# Sche_MCU_IO.net
KiCad netlist of a schematic drawn in Altium Designer
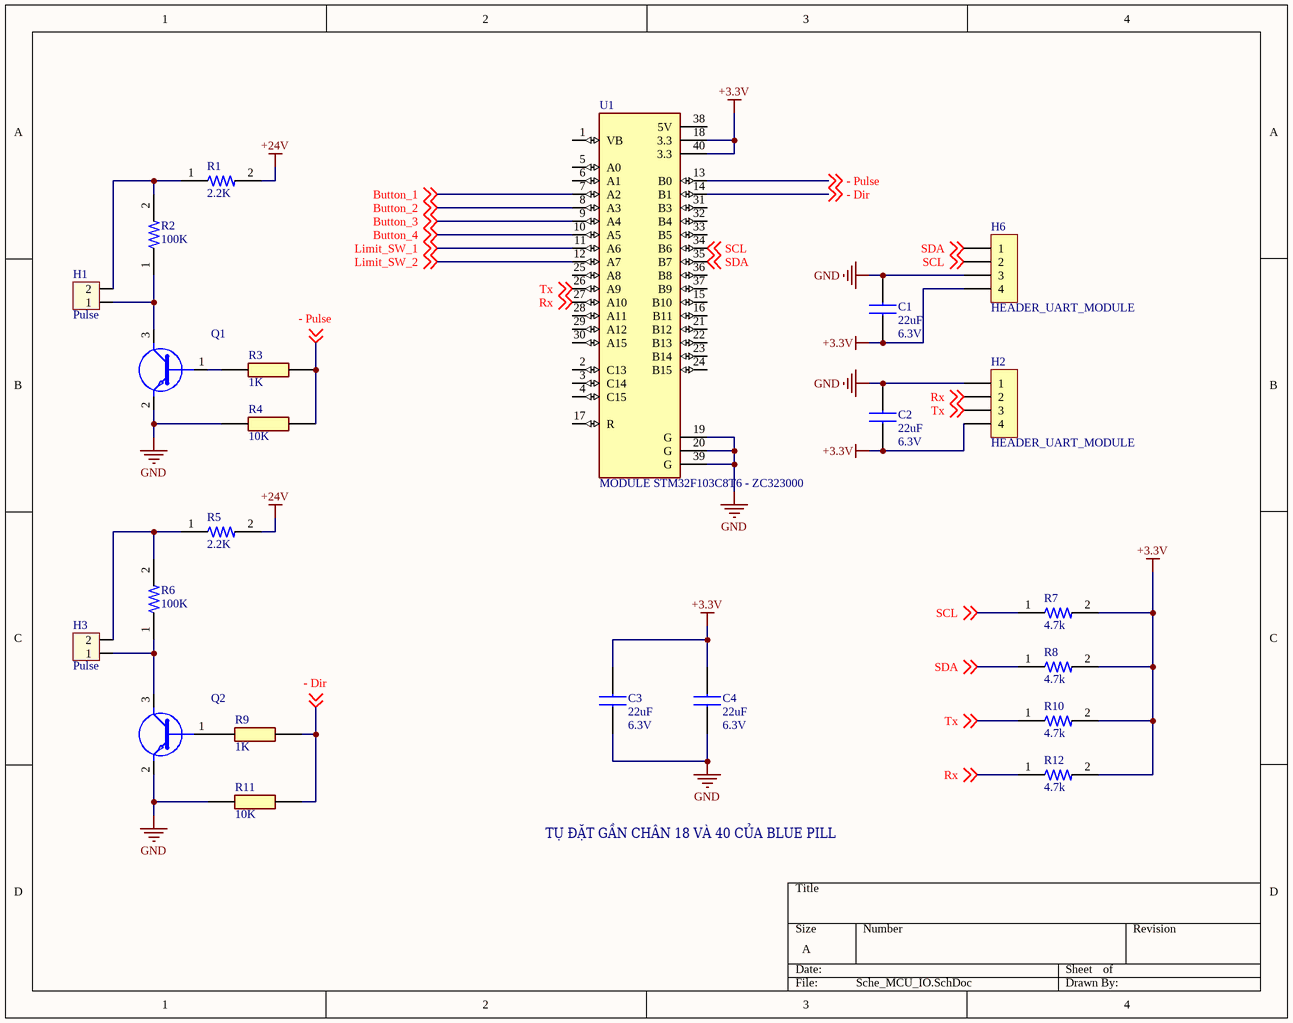
[diagram p0: Sche_MCU_IO.SchDoc]

(export (version "E")
  (design (tool "Eeschema 10.0.6"))
  (components
    (comp (ref "C1")
      (value "22uF")
      (footprint "PCB_COF_1.2:C 0603")
      (description "CAP CER 22UF 6.3V X5R 0603")
      (fields (field (name "ALTIUM_UNNAMED_1") "6.3V"))
      (libsource (lib "LAB_COATING COF_MACHINE") (part "CAP CER 22UF 6.3V X5R 0603 - GRM188R60J226MEA0D"))
    )
    (comp (ref "C2")
      (value "22uF")
      (footprint "PCB_COF_1.2:C 0603")
      (description "CAP CER 22UF 6.3V X5R 0603")
      (fields (field (name "ALTIUM_UNNAMED_1") "6.3V"))
      (libsource (lib "LAB_COATING COF_MACHINE") (part "CAP CER 22UF 6.3V X5R 0603 - GRM188R60J226MEA0D"))
    )
    (comp (ref "C3")
      (value "22uF")
      (footprint "PCB_COF_1.2:C 0603")
      (description "CAP CER 22UF 6.3V X5R 0603")
      (fields (field (name "ALTIUM_UNNAMED_1") "6.3V"))
      (libsource (lib "LAB_COATING COF_MACHINE") (part "CAP CER 22UF 6.3V X5R 0603 - GRM188R60J226MEA0D"))
    )
    (comp (ref "C4")
      (value "22uF")
      (footprint "PCB_COF_1.2:C 0603")
      (description "CAP CER 22UF 6.3V X5R 0603")
      (fields (field (name "ALTIUM_UNNAMED_1") "6.3V"))
      (libsource (lib "LAB_COATING COF_MACHINE") (part "CAP CER 22UF 6.3V X5R 0603 - GRM188R60J226MEA0D"))
    )
    (comp (ref "H1")
      (value "Pulse")
      (footprint "Header 2P DC 2.54")
      (description "Cắm")
      (libsource (lib "LAB_COATING COF_MACHINE") (part "Header 2P 2.54 Duc Cong"))
    )
    (comp (ref "H2")
      (value "HEADER_UART_MODULE")
      (footprint "XH2.54M-4")
      (description "Cắm")
      (libsource (lib "LAB_COATING COF_MACHINE") (part "Header 4P 2.54 Duc Thang"))
    )
    (comp (ref "H3")
      (value "Pulse")
      (footprint "Header 2P DC 2.54")
      (description "Cắm")
      (libsource (lib "LAB_COATING COF_MACHINE") (part "Header 2P 2.54 Duc Cong"))
    )
    (comp (ref "H6")
      (value "HEADER_UART_MODULE")
      (footprint "XH2.54M-4")
      (description "Cắm")
      (libsource (lib "LAB_COATING COF_MACHINE") (part "Header 4P 2.54 Duc Thang"))
    )
    (comp (ref "Q1")
      (value "TRANS NPN 45V 0.8A SOT23-3 - BCW66GLT1G")
      (footprint "SOT95P237X111-3N")
      (description "TRANS NPN 45V 0.8A SOT23-3")
      (fields
        (field (name "MANUFACTURER_PART_NUMBER") "BCW66GLT1G")
        (field (name "MOUSER PART NUMBER") "863-BCW66GLT1G")
      )
      (libsource (lib "LAB_COATING COF_MACHINE") (part "TRANS NPN 45V 0.8A SOT23-3 - BCW66GLT1G"))
    )
    (comp (ref "Q2")
      (value "TRANS NPN 45V 0.8A SOT23-3 - BCW66GLT1G")
      (footprint "SOT95P237X111-3N")
      (description "TRANS NPN 45V 0.8A SOT23-3")
      (fields
        (field (name "MANUFACTURER_PART_NUMBER") "BCW66GLT1G")
        (field (name "MOUSER PART NUMBER") "863-BCW66GLT1G")
      )
      (libsource (lib "LAB_COATING COF_MACHINE") (part "TRANS NPN 45V 0.8A SOT23-3 - BCW66GLT1G"))
    )
    (comp (ref "R1")
      (value "2.2K")
      (footprint "RES 0805")
      (description "RES SMD 2.2K OHM 5% 1/2W 0805")
      (fields (field (name "MP") "ERJ-P06J222V") (field (name "MF") "PANASONIC"))
      (libsource (lib "LAB_COATING COF_MACHINE") (part "RES SMD 2.2K OHM 5% 1/2W 0805 - ERJ-P06J222V"))
    )
    (comp (ref "R2")
      (value "100K")
      (footprint "Res 0603")
      (description "RES SMD 100K OHM 1% 1/10W 0603")
      (fields (field (name "MP") "CRCW0603100KFKEA") (field (name "MF") "Yageo"))
      (libsource (lib "LAB_COATING COF_MACHINE") (part "RES SMD 100K OHM 1% 1/10W 0603 - CRCW0603100KFKEA"))
    )
    (comp (ref "R3")
      (value "1K")
      (footprint "ERJ3EKF1000V")
      (description "RES SMD 1K OHM 5% 1/10W 0603")
      (fields
        (field (name "MANUFACTURER_PART_NUMBER") "ERJ-3GEYJ102V")
        (field (name "MOUSER PART NUMBER") "667-ERJ-3GEYJ102V")
      )
      (libsource (lib "LAB_COATING COF_MACHINE") (part "RES SMD 1K OHM 5% 1/10W 0603 - ERJ-3GEYJ102V"))
    )
    (comp (ref "R4")
      (value "10K")
      (footprint "ERJ3EKF1000V")
      (description "RES SMD 10K OHM 5% 1/10W 0603")
      (fields
        (field (name "MANUFACTURER_PART_NUMBER") "ERJ3GEYJ103V")
        (field (name "MOUSER PART NUMBER") "667-ERJ-3GEYJ103V")
      )
      (libsource (lib "LAB_COATING COF_MACHINE") (part "RES SMD 10K OHM 5% 1/10W 0603 - ERJ3GEYJ103V"))
    )
    (comp (ref "R5")
      (value "2.2K")
      (footprint "RES 0805")
      (description "RES SMD 2.2K OHM 5% 1/2W 0805")
      (fields (field (name "MP") "ERJ-P06J222V") (field (name "MF") "PANASONIC"))
      (libsource (lib "LAB_COATING COF_MACHINE") (part "RES SMD 2.2K OHM 5% 1/2W 0805 - ERJ-P06J222V"))
    )
    (comp (ref "R6")
      (value "100K")
      (footprint "Res 0603")
      (description "RES SMD 100K OHM 1% 1/10W 0603")
      (fields (field (name "MP") "CRCW0603100KFKEA") (field (name "MF") "Yageo"))
      (libsource (lib "LAB_COATING COF_MACHINE") (part "RES SMD 100K OHM 1% 1/10W 0603 - CRCW0603100KFKEA"))
    )
    (comp (ref "R7")
      (value "4.7k")
      (footprint "Res 0603")
      (description "RES 4.7K OHM 1% 1/10W 0603")
      (fields (field (name "MP") "RC0603FR-074K7L") (field (name "MF") "Yageo"))
      (libsource (lib "LAB_COATING COF_MACHINE") (part "RES 4.7K OHM 1% 1/10W 0603 - RC0603FR-074K7L"))
    )
    (comp (ref "R8")
      (value "4.7k")
      (footprint "Res 0603")
      (description "RES 4.7K OHM 1% 1/10W 0603")
      (fields (field (name "MP") "RC0603FR-074K7L") (field (name "MF") "Yageo"))
      (libsource (lib "LAB_COATING COF_MACHINE") (part "RES 4.7K OHM 1% 1/10W 0603 - RC0603FR-074K7L"))
    )
    (comp (ref "R9")
      (value "1K")
      (footprint "ERJ3EKF1000V")
      (description "RES SMD 1K OHM 5% 1/10W 0603")
      (fields
        (field (name "MANUFACTURER_PART_NUMBER") "ERJ-3GEYJ102V")
        (field (name "MOUSER PART NUMBER") "667-ERJ-3GEYJ102V")
      )
      (libsource (lib "LAB_COATING COF_MACHINE") (part "RES SMD 1K OHM 5% 1/10W 0603 - ERJ-3GEYJ102V"))
    )
    (comp (ref "R10")
      (value "4.7k")
      (footprint "Res 0603")
      (description "RES 4.7K OHM 1% 1/10W 0603")
      (fields (field (name "MP") "RC0603FR-074K7L") (field (name "MF") "Yageo"))
      (libsource (lib "LAB_COATING COF_MACHINE") (part "RES 4.7K OHM 1% 1/10W 0603 - RC0603FR-074K7L"))
    )
    (comp (ref "R11")
      (value "10K")
      (footprint "ERJ3EKF1000V")
      (description "RES SMD 10K OHM 5% 1/10W 0603")
      (fields
        (field (name "MANUFACTURER_PART_NUMBER") "ERJ3GEYJ103V")
        (field (name "MOUSER PART NUMBER") "667-ERJ-3GEYJ103V")
      )
      (libsource (lib "LAB_COATING COF_MACHINE") (part "RES SMD 10K OHM 5% 1/10W 0603 - ERJ3GEYJ103V"))
    )
    (comp (ref "R12")
      (value "4.7k")
      (footprint "Res 0603")
      (description "RES 4.7K OHM 1% 1/10W 0603")
      (fields (field (name "MP") "RC0603FR-074K7L") (field (name "MF") "Yageo"))
      (libsource (lib "LAB_COATING COF_MACHINE") (part "RES 4.7K OHM 1% 1/10W 0603 - RC0603FR-074K7L"))
    )
    (comp (ref "U1")
      (value "MODULE STM32F103C8T6 - ZC323000")
      (footprint "STM32F103C8T6_BluePill:MODULE_ZC323000")
      (description "MODULE STM32F103C8T6")
      (fields (field (name "MP") "ZC323000"))
      (libsource (lib "LAB_COATING COF_MACHINE") (part "MODULE STM32F103C8T6 - ZC323000"))
    )
  )
  (nets
    (net (code "1") (name "+3.3V") (class "Default")
      (node (ref "C1") (pin "1") (pinfunction "1_1") (pintype "passive"))
      (node (ref "C2") (pin "1") (pinfunction "1_1") (pintype "passive"))
      (node (ref "C3") (pin "2") (pinfunction "2_2") (pintype "passive"))
      (node (ref "C4") (pin "2") (pinfunction "2_2") (pintype "passive"))
      (node (ref "H2") (pin "4") (pinfunction "4_4") (pintype "passive"))
      (node (ref "H6") (pin "4") (pinfunction "4_4") (pintype "passive"))
      (node (ref "R10") (pin "2") (pinfunction "2_2") (pintype "passive"))
      (node (ref "R12") (pin "2") (pinfunction "2_2") (pintype "passive"))
      (node (ref "R7") (pin "2") (pinfunction "2_2") (pintype "passive"))
      (node (ref "R8") (pin "2") (pinfunction "2_2") (pintype "passive"))
      (node (ref "U1") (pin "18") (pinfunction "3.3_18") (pintype "power_in"))
      (node (ref "U1") (pin "40") (pinfunction "3.3_40") (pintype "power_in"))
    )
    (net (code "2") (name "+24V") (class "Default")
      (node (ref "R1") (pin "2") (pinfunction "2_2") (pintype "passive"))
      (node (ref "R5") (pin "2") (pinfunction "2_2") (pintype "passive"))
    )
    (net (code "3") (name "- Dir") (class "Default")
      (node (ref "R11") (pin "2") (pinfunction "2_2") (pintype "passive"))
      (node (ref "R9") (pin "2") (pinfunction "2_2") (pintype "passive"))
      (node (ref "U1") (pin "14") (pinfunction "B1_14") (pintype "bidirectional"))
    )
    (net (code "4") (name "- Pulse") (class "Default")
      (node (ref "R3") (pin "2") (pinfunction "2_2") (pintype "passive"))
      (node (ref "R4") (pin "2") (pinfunction "2_2") (pintype "passive"))
      (node (ref "U1") (pin "13") (pinfunction "B0_13") (pintype "bidirectional"))
    )
    (net (code "5") (name "Button_1") (class "Default")
      (node (ref "U1") (pin "7") (pinfunction "A2_7") (pintype "bidirectional"))
    )
    (net (code "6") (name "Button_2") (class "Default")
      (node (ref "U1") (pin "8") (pinfunction "A3_8") (pintype "bidirectional"))
    )
    (net (code "7") (name "Button_3") (class "Default")
      (node (ref "U1") (pin "9") (pinfunction "A4_9") (pintype "bidirectional"))
    )
    (net (code "8") (name "Button_4") (class "Default")
      (node (ref "U1") (pin "10") (pinfunction "A5_10") (pintype "bidirectional"))
    )
    (net (code "9") (name "GND") (class "Default")
      (node (ref "C1") (pin "2") (pinfunction "2_2") (pintype "passive"))
      (node (ref "C2") (pin "2") (pinfunction "2_2") (pintype "passive"))
      (node (ref "C3") (pin "1") (pinfunction "1_1") (pintype "passive"))
      (node (ref "C4") (pin "1") (pinfunction "1_1") (pintype "passive"))
      (node (ref "H2") (pin "1") (pinfunction "1_1") (pintype "passive"))
      (node (ref "H6") (pin "3") (pinfunction "3_3") (pintype "passive"))
      (node (ref "Q1") (pin "2") (pinfunction "E_2") (pintype "passive"))
      (node (ref "Q2") (pin "2") (pinfunction "E_2") (pintype "passive"))
      (node (ref "R11") (pin "1") (pinfunction "1_1") (pintype "passive"))
      (node (ref "R4") (pin "1") (pinfunction "1_1") (pintype "passive"))
      (node (ref "U1") (pin "19") (pinfunction "G_19") (pintype "power_in"))
      (node (ref "U1") (pin "20") (pinfunction "G_20") (pintype "power_in"))
      (node (ref "U1") (pin "39") (pinfunction "G_39") (pintype "power_in"))
    )
    (net (code "10") (name "Limit_SW_1") (class "Default")
      (node (ref "U1") (pin "11") (pinfunction "A6_11") (pintype "bidirectional"))
    )
    (net (code "11") (name "Limit_SW_2") (class "Default")
      (node (ref "U1") (pin "12") (pinfunction "A7_12") (pintype "bidirectional"))
    )
    (net (code "12") (name "Net-(H1-Pad2)") (class "Default")
      (node (ref "H1") (pin "2") (pinfunction "2_2") (pintype "passive"))
      (node (ref "R1") (pin "1") (pinfunction "1_1") (pintype "passive"))
      (node (ref "R2") (pin "2") (pinfunction "2_2") (pintype "passive"))
    )
    (net (code "13") (name "Net-(H3-Pad2)") (class "Default")
      (node (ref "H3") (pin "2") (pinfunction "2_2") (pintype "passive"))
      (node (ref "R5") (pin "1") (pinfunction "1_1") (pintype "passive"))
      (node (ref "R6") (pin "2") (pinfunction "2_2") (pintype "passive"))
    )
    (net (code "14") (name "Net-(Q1-B)") (class "Default")
      (node (ref "Q1") (pin "1") (pinfunction "B_1") (pintype "passive"))
      (node (ref "R3") (pin "1") (pinfunction "1_1") (pintype "passive"))
    )
    (net (code "15") (name "Net-(Q1-C)") (class "Default")
      (node (ref "H1") (pin "1") (pinfunction "1_1") (pintype "passive"))
      (node (ref "Q1") (pin "3") (pinfunction "C_3") (pintype "passive"))
      (node (ref "R2") (pin "1") (pinfunction "1_1") (pintype "passive"))
    )
    (net (code "16") (name "Net-(Q2-B)") (class "Default")
      (node (ref "Q2") (pin "1") (pinfunction "B_1") (pintype "passive"))
      (node (ref "R9") (pin "1") (pinfunction "1_1") (pintype "passive"))
    )
    (net (code "17") (name "Net-(Q2-C)") (class "Default")
      (node (ref "H3") (pin "1") (pinfunction "1_1") (pintype "passive"))
      (node (ref "Q2") (pin "3") (pinfunction "C_3") (pintype "passive"))
      (node (ref "R6") (pin "1") (pinfunction "1_1") (pintype "passive"))
    )
    (net (code "18") (name "Rx") (class "Default")
      (node (ref "H2") (pin "2") (pinfunction "2_2") (pintype "passive"))
      (node (ref "R12") (pin "1") (pinfunction "1_1") (pintype "passive"))
      (node (ref "U1") (pin "27") (pinfunction "A10_27") (pintype "bidirectional"))
    )
    (net (code "19") (name "SCL") (class "Default")
      (node (ref "H6") (pin "2") (pinfunction "2_2") (pintype "passive"))
      (node (ref "R7") (pin "1") (pinfunction "1_1") (pintype "passive"))
      (node (ref "U1") (pin "34") (pinfunction "B6_34") (pintype "bidirectional"))
    )
    (net (code "20") (name "SDA") (class "Default")
      (node (ref "H6") (pin "1") (pinfunction "1_1") (pintype "passive"))
      (node (ref "R8") (pin "1") (pinfunction "1_1") (pintype "passive"))
      (node (ref "U1") (pin "35") (pinfunction "B7_35") (pintype "bidirectional"))
    )
    (net (code "21") (name "Tx") (class "Default")
      (node (ref "H2") (pin "3") (pinfunction "3_3") (pintype "passive"))
      (node (ref "R10") (pin "1") (pinfunction "1_1") (pintype "passive"))
      (node (ref "U1") (pin "26") (pinfunction "A9_26") (pintype "bidirectional"))
    )
    (net (code "22") (name "unconnected-(U1-5V-Pad38)") (class "Default")
      (node (ref "U1") (pin "38") (pinfunction "5V_38") (pintype "power_in"))
    )
    (net (code "23") (name "unconnected-(U1-A0-Pad5)") (class "Default")
      (node (ref "U1") (pin "5") (pinfunction "A0_5") (pintype "bidirectional"))
    )
    (net (code "24") (name "unconnected-(U1-A1-Pad6)") (class "Default")
      (node (ref "U1") (pin "6") (pinfunction "A1_6") (pintype "bidirectional"))
    )
    (net (code "25") (name "unconnected-(U1-A8-Pad25)") (class "Default")
      (node (ref "U1") (pin "25") (pinfunction "A8_25") (pintype "bidirectional"))
    )
    (net (code "26") (name "unconnected-(U1-A11-Pad28)") (class "Default")
      (node (ref "U1") (pin "28") (pinfunction "A11_28") (pintype "bidirectional"))
    )
    (net (code "27") (name "unconnected-(U1-A12-Pad29)") (class "Default")
      (node (ref "U1") (pin "29") (pinfunction "A12_29") (pintype "bidirectional"))
    )
    (net (code "28") (name "unconnected-(U1-A15-Pad30)") (class "Default")
      (node (ref "U1") (pin "30") (pinfunction "A15_30") (pintype "bidirectional"))
    )
    (net (code "29") (name "unconnected-(U1-B3-Pad31)") (class "Default")
      (node (ref "U1") (pin "31") (pinfunction "B3_31") (pintype "bidirectional"))
    )
    (net (code "30") (name "unconnected-(U1-B4-Pad32)") (class "Default")
      (node (ref "U1") (pin "32") (pinfunction "B4_32") (pintype "bidirectional"))
    )
    (net (code "31") (name "unconnected-(U1-B5-Pad33)") (class "Default")
      (node (ref "U1") (pin "33") (pinfunction "B5_33") (pintype "bidirectional"))
    )
    (net (code "32") (name "unconnected-(U1-B8-Pad36)") (class "Default")
      (node (ref "U1") (pin "36") (pinfunction "B8_36") (pintype "bidirectional"))
    )
    (net (code "33") (name "unconnected-(U1-B9-Pad37)") (class "Default")
      (node (ref "U1") (pin "37") (pinfunction "B9_37") (pintype "bidirectional"))
    )
    (net (code "34") (name "unconnected-(U1-B10-Pad15)") (class "Default")
      (node (ref "U1") (pin "15") (pinfunction "B10_15") (pintype "bidirectional"))
    )
    (net (code "35") (name "unconnected-(U1-B11-Pad16)") (class "Default")
      (node (ref "U1") (pin "16") (pinfunction "B11_16") (pintype "bidirectional"))
    )
    (net (code "36") (name "unconnected-(U1-B12-Pad21)") (class "Default")
      (node (ref "U1") (pin "21") (pinfunction "B12_21") (pintype "bidirectional"))
    )
    (net (code "37") (name "unconnected-(U1-B13-Pad22)") (class "Default")
      (node (ref "U1") (pin "22") (pinfunction "B13_22") (pintype "bidirectional"))
    )
    (net (code "38") (name "unconnected-(U1-B14-Pad23)") (class "Default")
      (node (ref "U1") (pin "23") (pinfunction "B14_23") (pintype "bidirectional"))
    )
    (net (code "39") (name "unconnected-(U1-B15-Pad24)") (class "Default")
      (node (ref "U1") (pin "24") (pinfunction "B15_24") (pintype "bidirectional"))
    )
    (net (code "40") (name "unconnected-(U1-C13-Pad2)") (class "Default")
      (node (ref "U1") (pin "2") (pinfunction "C13_2") (pintype "bidirectional"))
    )
    (net (code "41") (name "unconnected-(U1-C14-Pad3)") (class "Default")
      (node (ref "U1") (pin "3") (pinfunction "C14_3") (pintype "bidirectional"))
    )
    (net (code "42") (name "unconnected-(U1-C15-Pad4)") (class "Default")
      (node (ref "U1") (pin "4") (pinfunction "C15_4") (pintype "bidirectional"))
    )
    (net (code "43") (name "unconnected-(U1-R-Pad17)") (class "Default")
      (node (ref "U1") (pin "17") (pinfunction "R_17") (pintype "bidirectional"))
    )
    (net (code "44") (name "unconnected-(U1-VB-Pad1)") (class "Default")
      (node (ref "U1") (pin "1") (pinfunction "VB_1") (pintype "bidirectional"))
    )
  )
)
